# Sheet1.net
KiCad netlist of a schematic drawn in Altium Designer
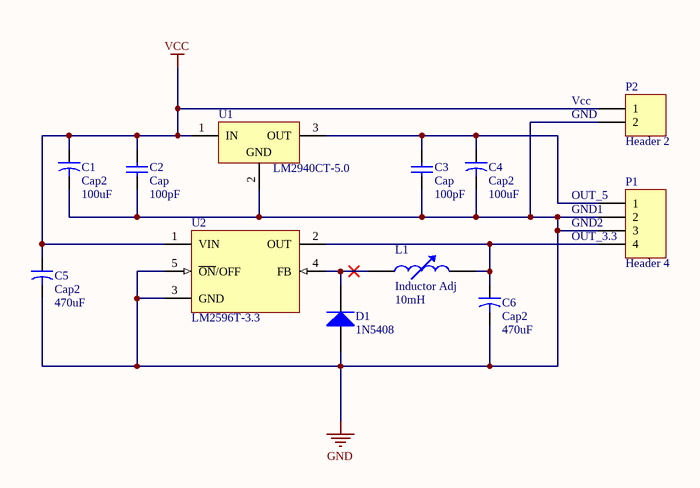
[diagram p0: Sheet1.SchDoc]

(export (version "E")
  (design (tool "Eeschema 10.0.6"))
  (components
    (comp (ref "C1")
      (value "Cap2")
      (footprint "CAPR5-4X5")
      (description "Capacitor")
      (fields (field (name "ALTIUM_VALUE") "100uF") (field (name "PUBLISHER") "Altium Limited"))
      (libsource (lib "Miscellaneous Devices") (part "Cap2"))
    )
    (comp (ref "C2")
      (value "Cap")
      (footprint "RAD-0.3")
      (description "Capacitor")
      (fields (field (name "ALTIUM_VALUE") "100pF") (field (name "PUBLISHER") "Altium Limited"))
      (libsource (lib "Miscellaneous Devices") (part "Cap"))
    )
    (comp (ref "C3")
      (value "Cap")
      (footprint "RAD-0.3")
      (description "Capacitor")
      (fields (field (name "ALTIUM_VALUE") "100pF") (field (name "PUBLISHER") "Altium Limited"))
      (libsource (lib "Miscellaneous Devices") (part "Cap"))
    )
    (comp (ref "C4")
      (value "Cap2")
      (footprint "CAPR5-4X5")
      (description "Capacitor")
      (fields (field (name "ALTIUM_VALUE") "100uF") (field (name "PUBLISHER") "Altium Limited"))
      (libsource (lib "Miscellaneous Devices") (part "Cap2"))
    )
    (comp (ref "C5")
      (value "Cap2")
      (footprint "CAPR5-4X5")
      (description "Capacitor")
      (fields (field (name "ALTIUM_VALUE") "470uF") (field (name "PUBLISHER") "Altium Limited"))
      (libsource (lib "Miscellaneous Devices") (part "Cap2"))
    )
    (comp (ref "C6")
      (value "Cap2")
      (footprint "CAPR5-4X5")
      (description "Capacitor")
      (fields (field (name "ALTIUM_VALUE") "470uF") (field (name "PUBLISHER") "Altium Limited"))
      (libsource (lib "Miscellaneous Devices") (part "Cap2"))
    )
    (comp (ref "D1")
      (value "1N5408")
      (footprint "DO-201AD")
      (description "3 Amp Medium Power Silicon Rectifier Diode")
      (fields (field (name "PUBLISHER") "Altium Limited"))
      (libsource (lib "IR Rectifier - Standard Recovery") (part "1N5408"))
    )
    (comp (ref "L1")
      (value "Inductor Adj")
      (footprint "AXIAL-0.8")
      (description "Adjustable Inductor")
      (fields (field (name "ALTIUM_VALUE") "10mH") (field (name "PUBLISHER") "Altium Limited"))
      (libsource (lib "Miscellaneous Devices") (part "Inductor Adj"))
    )
    (comp (ref "P1")
      (value "Header 4")
      (footprint "HDR1X4")
      (description "Header, 4-Pin")
      (fields (field (name "PUBLISHER") "Altium Limited"))
      (libsource (lib "Miscellaneous Connectors") (part "Header 4"))
    )
    (comp (ref "P2")
      (value "Header 2")
      (footprint "HDR1X2")
      (description "Header, 2-Pin")
      (fields (field (name "PUBLISHER") "Altium Limited"))
      (libsource (lib "Miscellaneous Connectors") (part "Header 2"))
    )
    (comp (ref "U1")
      (value "LM2940CT-5.0")
      (footprint "T03B")
      (description "1A Low Dropout Regulator, 3-pin TO-220")
      (fields
        (field (name "MANUFACTURER") "National Semiconductor")
        (field (name "PUBLISHER") "Altium Limited")
      )
      (libsource (lib "NSC LDO") (part "LM2940CT-5.0"))
    )
    (comp (ref "U2")
      (value "LM2596T-3.3")
      (footprint "T05D")
      (description "SIMPLE SWITCHER?Power Converter 150 KHz 3A Step-Down Voltage Regulator, 5-pin TO-220")
      (fields
        (field (name "MANUFACTURER") "National Semiconductor")
        (field (name "PUBLISHER") "Altium Limited")
      )
      (libsource (lib "NSC Switcher") (part "LM2596T-3.3"))
    )
  )
  (nets
    (net (code "1") (name "GND") (class "Default")
      (node (ref "C1") (pin "2") (pinfunction "2_2") (pintype "passive"))
      (node (ref "C2") (pin "1") (pinfunction "1_1") (pintype "passive"))
      (node (ref "C3") (pin "1") (pinfunction "1_1") (pintype "passive"))
      (node (ref "C4") (pin "2") (pinfunction "2_2") (pintype "passive"))
      (node (ref "C5") (pin "2") (pinfunction "2_2") (pintype "passive"))
      (node (ref "C6") (pin "2") (pinfunction "2_2") (pintype "passive"))
      (node (ref "D1") (pin "1") (pinfunction "A_1") (pintype "passive"))
      (node (ref "P1") (pin "2") (pinfunction "2_2") (pintype "passive"))
      (node (ref "P1") (pin "3") (pinfunction "3_3") (pintype "passive"))
      (node (ref "P2") (pin "2") (pinfunction "2_2") (pintype "passive"))
      (node (ref "U1") (pin "2") (pinfunction "GND_2") (pintype "power_in"))
      (node (ref "U2") (pin "3") (pinfunction "GND_3") (pintype "power_in"))
      (node (ref "U2") (pin "5") (pinfunction "~{ON}/OFF_5") (pintype "input"))
    )
    (net (code "2") (name "Net-(D1-K)") (class "Default")
      (node (ref "D1") (pin "2") (pinfunction "K_2") (pintype "passive"))
      (node (ref "L1") (pin "1") (pinfunction "1_1") (pintype "passive"))
      (node (ref "U2") (pin "4") (pinfunction "FB_4") (pintype "input"))
    )
    (net (code "3") (name "Net-(U1-OUT)") (class "Default")
      (node (ref "C3") (pin "2") (pinfunction "2_2") (pintype "passive"))
      (node (ref "C4") (pin "1") (pinfunction "1_1") (pintype "passive"))
      (node (ref "P1") (pin "1") (pinfunction "1_1") (pintype "passive"))
      (node (ref "U1") (pin "3") (pinfunction "OUT_3") (pintype "power_in"))
    )
    (net (code "4") (name "Net-(U2-OUT)") (class "Default")
      (node (ref "C6") (pin "1") (pinfunction "1_1") (pintype "passive"))
      (node (ref "L1") (pin "2") (pinfunction "2_2") (pintype "passive"))
      (node (ref "P1") (pin "4") (pinfunction "4_4") (pintype "passive"))
      (node (ref "U2") (pin "2") (pinfunction "OUT_2") (pintype "power_in"))
    )
    (net (code "5") (name "VCC") (class "Default")
      (node (ref "C1") (pin "1") (pinfunction "1_1") (pintype "passive"))
      (node (ref "C2") (pin "2") (pinfunction "2_2") (pintype "passive"))
      (node (ref "C5") (pin "1") (pinfunction "1_1") (pintype "passive"))
      (node (ref "P2") (pin "1") (pinfunction "1_1") (pintype "passive"))
      (node (ref "U1") (pin "1") (pinfunction "IN_1") (pintype "power_in"))
      (node (ref "U2") (pin "1") (pinfunction "VIN_1") (pintype "power_in"))
    )
  )
)
